# sideMICRO.net
KiCad netlist of a schematic drawn in Altium Designer
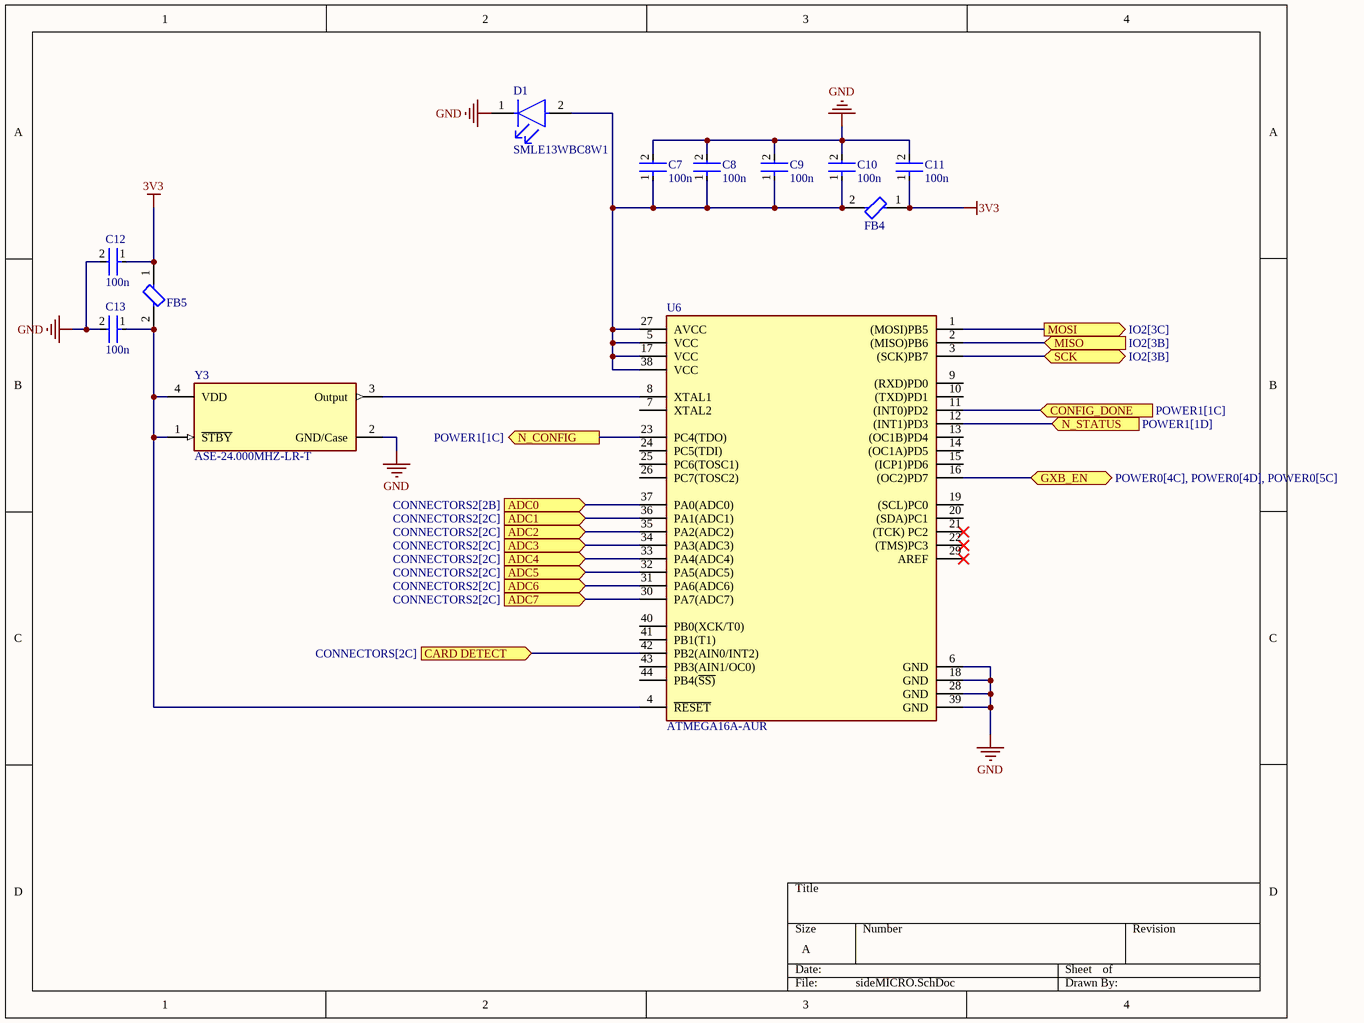
[diagram p0: sideMICRO.SchDoc]

(export (version "E")
  (design (tool "Eeschema 10.0.6"))
  (components
    (comp (ref "C7")
      (value "100n")
      (footprint "FP-CL10-IPC_C")
      (description "Cap Ceramic 4.7uF 10V X5R ±10% Pad SMD 0603 +85°C T/R")
      (fields (field (name "TOLERANCE") "10%"))
      (libsource (lib "Altium Content Vault") (part "b4654b650e69147ec39a6b967a45e02"))
    )
    (comp (ref "C8")
      (value "100n")
      (footprint "FP-CL10-IPC_C")
      (description "Cap Ceramic 4.7uF 10V X5R ±10% Pad SMD 0603 +85°C T/R")
      (fields (field (name "TOLERANCE") "10%"))
      (libsource (lib "Altium Content Vault") (part "b4654b650e69147ec39a6b967a45e02"))
    )
    (comp (ref "C9")
      (value "100n")
      (footprint "FP-CL10-IPC_C")
      (description "Cap Ceramic 4.7uF 10V X5R ±10% Pad SMD 0603 +85°C T/R")
      (fields (field (name "TOLERANCE") "10%"))
      (libsource (lib "Altium Content Vault") (part "b4654b650e69147ec39a6b967a45e02"))
    )
    (comp (ref "C10")
      (value "100n")
      (footprint "FP-CL10-IPC_C")
      (description "Cap Ceramic 4.7uF 10V X5R ±10% Pad SMD 0603 +85°C T/R")
      (fields (field (name "TOLERANCE") "10%"))
      (libsource (lib "Altium Content Vault") (part "b4654b650e69147ec39a6b967a45e02"))
    )
    (comp (ref "C11")
      (value "100n")
      (footprint "FP-CL10-IPC_C")
      (description "Cap Ceramic 4.7uF 10V X5R ±10% Pad SMD 0603 +85°C T/R")
      (fields (field (name "TOLERANCE") "10%"))
      (libsource (lib "Altium Content Vault") (part "b4654b650e69147ec39a6b967a45e02"))
    )
    (comp (ref "C12")
      (value "100n")
      (footprint "FP-CL10-IPC_C")
      (description "Cap Ceramic 4.7uF 10V X5R ±10% Pad SMD 0603 +85°C T/R")
      (fields (field (name "TOLERANCE") "10%"))
      (libsource (lib "Altium Content Vault") (part "b4654b650e69147ec39a6b967a45e02"))
    )
    (comp (ref "C13")
      (value "100n")
      (footprint "FP-CL10-IPC_C")
      (description "Cap Ceramic 4.7uF 10V X5R ±10% Pad SMD 0603 +85°C T/R")
      (fields (field (name "TOLERANCE") "10%"))
      (libsource (lib "Altium Content Vault") (part "b4654b650e69147ec39a6b967a45e02"))
    )
    (comp (ref "D1")
      (value "SMLE13WBC8W1")
      (footprint "FP-SMLE13WBC8W1-MFG")
      (description "LED WHITE 0603 SMD")
      (fields
        (field (name "OCTOPART") "https://octopart.com/smle13wbc8w1-rohm-22224565")
        (field (name "MANUFACTURER") "Rohm")
      )
      (libsource (lib "Altium Content Vault") (part "8706943c75ba83719d021d2fdc84c58"))
    )
    (comp (ref "FB4")
      (value "BLM18KG121TN1D")
      (footprint "FP-BLM18-0_15-t0_6-d1_2-IPC_A")
      (description "FERRITE BEAD 120 OHM 0603 1LN")
      (fields (field (name "TOLERANCE") "25%"))
      (libsource (lib "Altium Content Vault") (part "5f30dd21d616792df468990f7003faa"))
    )
    (comp (ref "FB5")
      (value "BLM18KG121TN1D")
      (footprint "FP-BLM18-0_15-t0_6-d1_2-IPC_A")
      (description "FERRITE BEAD 120 OHM 0603 1LN")
      (fields (field (name "TOLERANCE") "25%"))
      (libsource (lib "Altium Content Vault") (part "5f30dd21d616792df468990f7003faa"))
    )
    (comp (ref "U6")
      (value "ATMEGA16A-AUR")
      (footprint "FP-44A-MFG")
      (description "IC MCU 8BIT 16KB FLASH 44TQFP")
      (libsource (lib "Altium Content Vault") (part "ed42ffdc3273df72733ccc2dd2ee123"))
    )
    (comp (ref "Y3")
      (value "ASE-24.000MHZ-LR-T")
      (footprint "FP-ASE-MFG")
      (description "XTAL Oscillator 24MHz ±25ppm CMOS 3.3V 4-SMD 3.2mm x 2.5mm")
      (libsource (lib "Altium Content Vault") (part "61a724e6190563596ac712fef61ad37"))
    )
  )
  (nets
    (net (code "1") (name "/ADC0") (class "Default")
      (node (ref "U6") (pin "37") (pinfunction "PA0(ADC0)_37") (pintype "passive"))
    )
    (net (code "2") (name "/ADC1") (class "Default")
      (node (ref "U6") (pin "36") (pinfunction "PA1(ADC1)_36") (pintype "passive"))
    )
    (net (code "3") (name "/ADC2") (class "Default")
      (node (ref "U6") (pin "35") (pinfunction "PA2(ADC2)_35") (pintype "passive"))
    )
    (net (code "4") (name "/ADC3") (class "Default")
      (node (ref "U6") (pin "34") (pinfunction "PA3(ADC3)_34") (pintype "passive"))
    )
    (net (code "5") (name "/ADC4") (class "Default")
      (node (ref "U6") (pin "33") (pinfunction "PA4(ADC4)_33") (pintype "passive"))
    )
    (net (code "6") (name "/ADC5") (class "Default")
      (node (ref "U6") (pin "32") (pinfunction "PA5(ADC5)_32") (pintype "passive"))
    )
    (net (code "7") (name "/ADC6") (class "Default")
      (node (ref "U6") (pin "31") (pinfunction "PA6(ADC6)_31") (pintype "passive"))
    )
    (net (code "8") (name "/ADC7") (class "Default")
      (node (ref "U6") (pin "30") (pinfunction "PA7(ADC7)_30") (pintype "passive"))
    )
    (net (code "9") (name "/CARD DETECT") (class "Default")
      (node (ref "U6") (pin "42") (pinfunction "PB2(AIN0/INT2)_42") (pintype "passive"))
    )
    (net (code "10") (name "/CONFIG_DONE") (class "Default")
      (node (ref "U6") (pin "11") (pinfunction "(INT0)PD2_11") (pintype "passive"))
    )
    (net (code "11") (name "/GXB_EN") (class "Default")
      (node (ref "U6") (pin "16") (pinfunction "(OC2)PD7_16") (pintype "passive"))
    )
    (net (code "12") (name "/MISO") (class "Default")
      (node (ref "U6") (pin "2") (pinfunction "(MISO)PB6_2") (pintype "passive"))
    )
    (net (code "13") (name "/MOSI") (class "Default")
      (node (ref "U6") (pin "1") (pinfunction "(MOSI)PB5_1") (pintype "passive"))
    )
    (net (code "14") (name "/N_CONFIG") (class "Default")
      (node (ref "U6") (pin "23") (pinfunction "PC4(TDO)_23") (pintype "passive"))
    )
    (net (code "15") (name "/N_STATUS") (class "Default")
      (node (ref "U6") (pin "12") (pinfunction "(INT1)PD3_12") (pintype "passive"))
    )
    (net (code "16") (name "/SCK") (class "Default")
      (node (ref "U6") (pin "3") (pinfunction "(SCK)PB7_3") (pintype "passive"))
    )
    (net (code "17") (name "3V3") (class "Default")
      (node (ref "C11") (pin "1") (pinfunction "1_1") (pintype "passive"))
      (node (ref "C12") (pin "1") (pinfunction "1_1") (pintype "passive"))
      (node (ref "FB4") (pin "1") (pinfunction "1_1") (pintype "passive"))
      (node (ref "FB5") (pin "1") (pinfunction "1_1") (pintype "passive"))
    )
    (net (code "18") (name "GND") (class "Default")
      (node (ref "C10") (pin "2") (pinfunction "2_2") (pintype "passive"))
      (node (ref "C11") (pin "2") (pinfunction "2_2") (pintype "passive"))
      (node (ref "C12") (pin "2") (pinfunction "2_2") (pintype "passive"))
      (node (ref "C13") (pin "2") (pinfunction "2_2") (pintype "passive"))
      (node (ref "C7") (pin "2") (pinfunction "2_2") (pintype "passive"))
      (node (ref "C8") (pin "2") (pinfunction "2_2") (pintype "passive"))
      (node (ref "C9") (pin "2") (pinfunction "2_2") (pintype "passive"))
      (node (ref "D1") (pin "1") (pinfunction "C_1") (pintype "passive"))
      (node (ref "U6") (pin "18") (pinfunction "GND_18") (pintype "passive"))
      (node (ref "U6") (pin "28") (pinfunction "GND_28") (pintype "passive"))
      (node (ref "U6") (pin "39") (pinfunction "GND_39") (pintype "passive"))
      (node (ref "U6") (pin "6") (pinfunction "GND_6") (pintype "passive"))
      (node (ref "Y3") (pin "2") (pinfunction "GND/Case_2") (pintype "power_in"))
    )
    (net (code "19") (name "Net-(D1-A)") (class "Default")
      (node (ref "C10") (pin "1") (pinfunction "1_1") (pintype "passive"))
      (node (ref "C7") (pin "1") (pinfunction "1_1") (pintype "passive"))
      (node (ref "C8") (pin "1") (pinfunction "1_1") (pintype "passive"))
      (node (ref "C9") (pin "1") (pinfunction "1_1") (pintype "passive"))
      (node (ref "D1") (pin "2") (pinfunction "A_2") (pintype "passive"))
      (node (ref "FB4") (pin "2") (pinfunction "2_2") (pintype "passive"))
      (node (ref "U6") (pin "17") (pinfunction "VCC_17") (pintype "passive"))
      (node (ref "U6") (pin "27") (pinfunction "AVCC_27") (pintype "passive"))
      (node (ref "U6") (pin "38") (pinfunction "VCC_38") (pintype "passive"))
      (node (ref "U6") (pin "5") (pinfunction "VCC_5") (pintype "passive"))
    )
    (net (code "20") (name "Net-(U6-XTAL1)") (class "Default")
      (node (ref "U6") (pin "8") (pinfunction "XTAL1_8") (pintype "passive"))
      (node (ref "Y3") (pin "3") (pinfunction "Output_3") (pintype "output"))
    )
    (net (code "21") (name "Net-(U6-~{RESET})") (class "Default")
      (node (ref "C13") (pin "1") (pinfunction "1_1") (pintype "passive"))
      (node (ref "FB5") (pin "2") (pinfunction "2_2") (pintype "passive"))
      (node (ref "U6") (pin "4") (pinfunction "~{RESET}_4") (pintype "passive"))
      (node (ref "Y3") (pin "1") (pinfunction "~{STBY}_1") (pintype "input"))
      (node (ref "Y3") (pin "4") (pinfunction "VDD_4") (pintype "power_in"))
    )
    (net (code "22") (name "unconnected-(U6-(ICP1)PD6-Pad15)") (class "Default")
      (node (ref "U6") (pin "15") (pinfunction "(ICP1)PD6_15") (pintype "passive"))
    )
    (net (code "23") (name "unconnected-(U6-(OC1A)PD5-Pad14)") (class "Default")
      (node (ref "U6") (pin "14") (pinfunction "(OC1A)PD5_14") (pintype "passive"))
    )
    (net (code "24") (name "unconnected-(U6-(OC1B)PD4-Pad13)") (class "Default")
      (node (ref "U6") (pin "13") (pinfunction "(OC1B)PD4_13") (pintype "passive"))
    )
    (net (code "25") (name "unconnected-(U6-(RXD)PD0-Pad9)") (class "Default")
      (node (ref "U6") (pin "9") (pinfunction "(RXD)PD0_9") (pintype "passive"))
    )
    (net (code "26") (name "unconnected-(U6-(SCL)PC0-Pad19)") (class "Default")
      (node (ref "U6") (pin "19") (pinfunction "(SCL)PC0_19") (pintype "passive"))
    )
    (net (code "27") (name "unconnected-(U6-(SDA)PC1-Pad20)") (class "Default")
      (node (ref "U6") (pin "20") (pinfunction "(SDA)PC1_20") (pintype "passive"))
    )
    (net (code "28") (name "unconnected-(U6-(TCK)_PC2-Pad21)") (class "Default")
      (node (ref "U6") (pin "21") (pinfunction "(TCK)_PC2_21") (pintype "passive+no_connect"))
    )
    (net (code "29") (name "unconnected-(U6-(TMS)PC3-Pad22)") (class "Default")
      (node (ref "U6") (pin "22") (pinfunction "(TMS)PC3_22") (pintype "passive+no_connect"))
    )
    (net (code "30") (name "unconnected-(U6-(TXD)PD1-Pad10)") (class "Default")
      (node (ref "U6") (pin "10") (pinfunction "(TXD)PD1_10") (pintype "passive"))
    )
    (net (code "31") (name "unconnected-(U6-AREF-Pad29)") (class "Default")
      (node (ref "U6") (pin "29") (pinfunction "AREF_29") (pintype "passive+no_connect"))
    )
    (net (code "32") (name "unconnected-(U6-PB0(XCK{slash}T0)-Pad40)") (class "Default")
      (node (ref "U6") (pin "40") (pinfunction "PB0(XCK/T0)_40") (pintype "passive"))
    )
    (net (code "33") (name "unconnected-(U6-PB1(T1)-Pad41)") (class "Default")
      (node (ref "U6") (pin "41") (pinfunction "PB1(T1)_41") (pintype "passive"))
    )
    (net (code "34") (name "unconnected-(U6-PB3(AIN1{slash}OC0)-Pad43)") (class "Default")
      (node (ref "U6") (pin "43") (pinfunction "PB3(AIN1/OC0)_43") (pintype "passive"))
    )
    (net (code "35") (name "unconnected-(U6-PB4(~{SS)}-Pad44)") (class "Default")
      (node (ref "U6") (pin "44") (pinfunction "PB4(~{SS)}_44") (pintype "passive"))
    )
    (net (code "36") (name "unconnected-(U6-PC5(TDI)-Pad24)") (class "Default")
      (node (ref "U6") (pin "24") (pinfunction "PC5(TDI)_24") (pintype "passive"))
    )
    (net (code "37") (name "unconnected-(U6-PC6(TOSC1)-Pad25)") (class "Default")
      (node (ref "U6") (pin "25") (pinfunction "PC6(TOSC1)_25") (pintype "passive"))
    )
    (net (code "38") (name "unconnected-(U6-PC7(TOSC2)-Pad26)") (class "Default")
      (node (ref "U6") (pin "26") (pinfunction "PC7(TOSC2)_26") (pintype "passive"))
    )
    (net (code "39") (name "unconnected-(U6-XTAL2-Pad7)") (class "Default")
      (node (ref "U6") (pin "7") (pinfunction "XTAL2_7") (pintype "passive"))
    )
  )
)
